# ai.net
KiCad netlist of a schematic drawn in Altium Designer
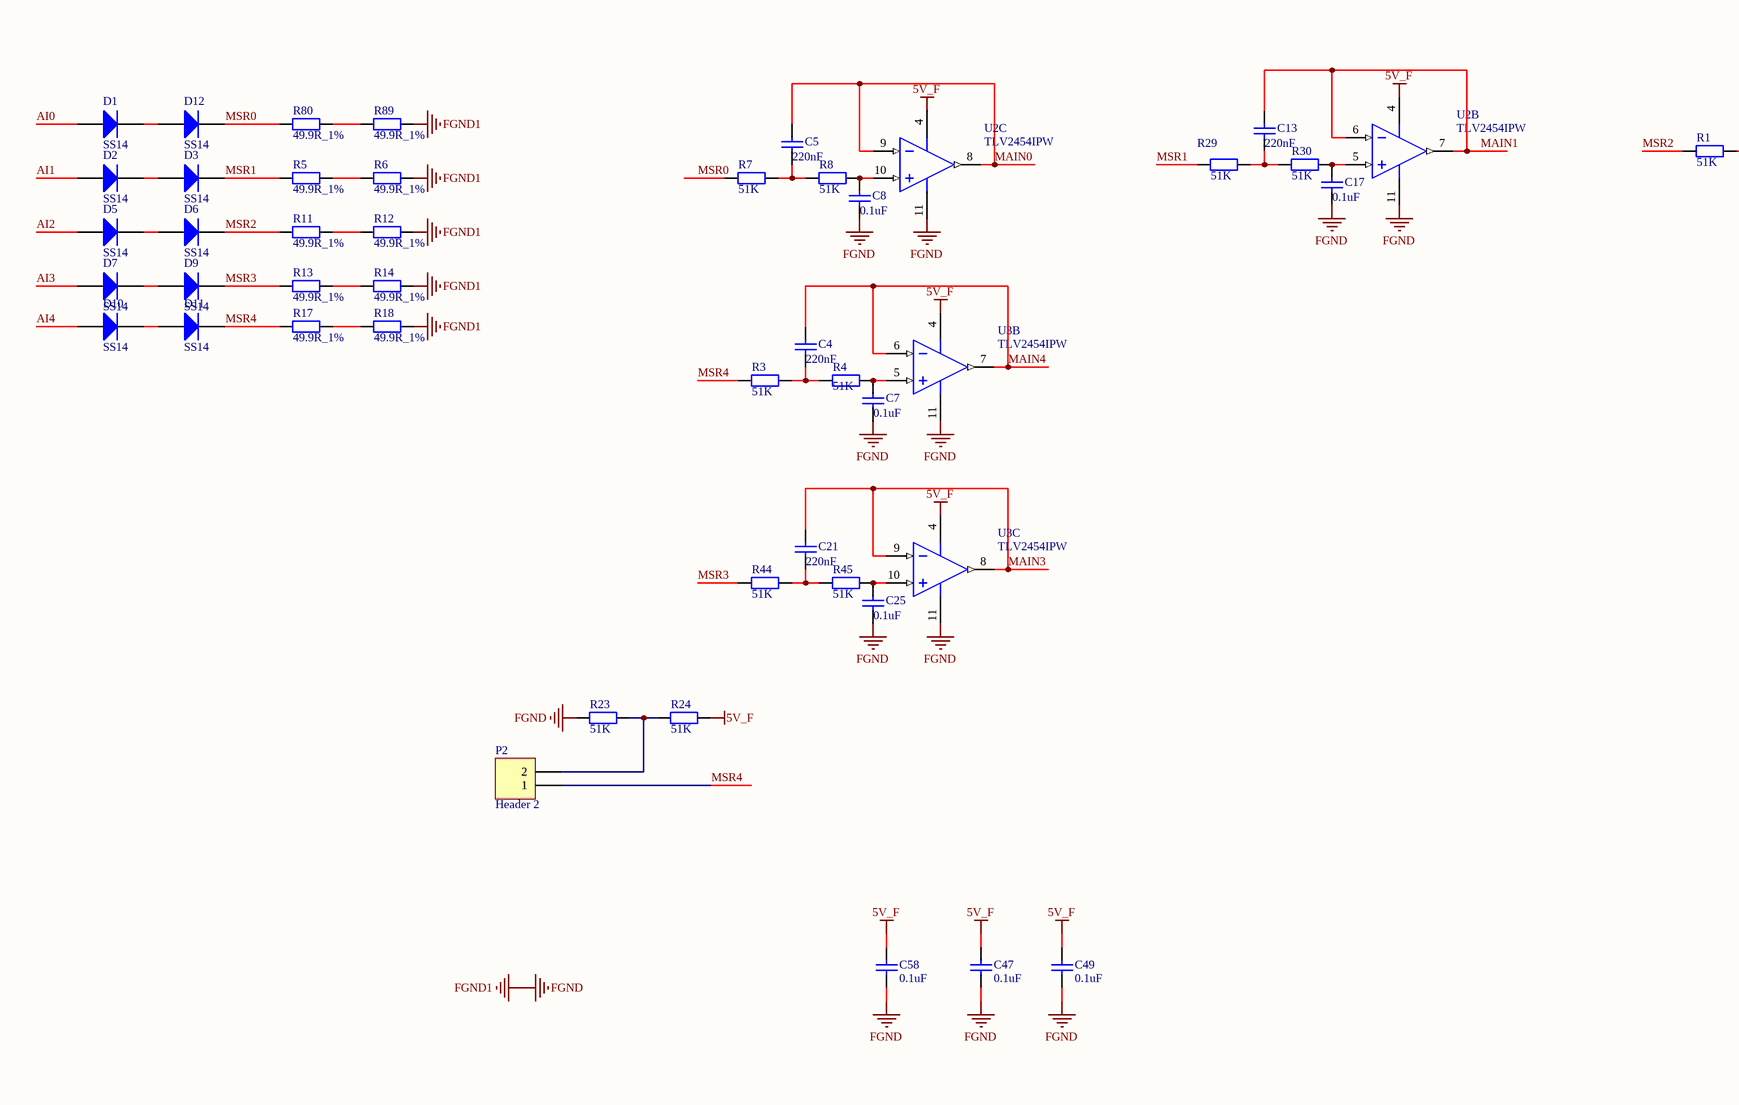
[diagram p0: ai.SchDoc, top left]
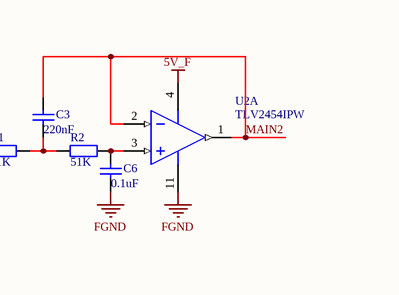
[diagram p1: ai.SchDoc, top right]
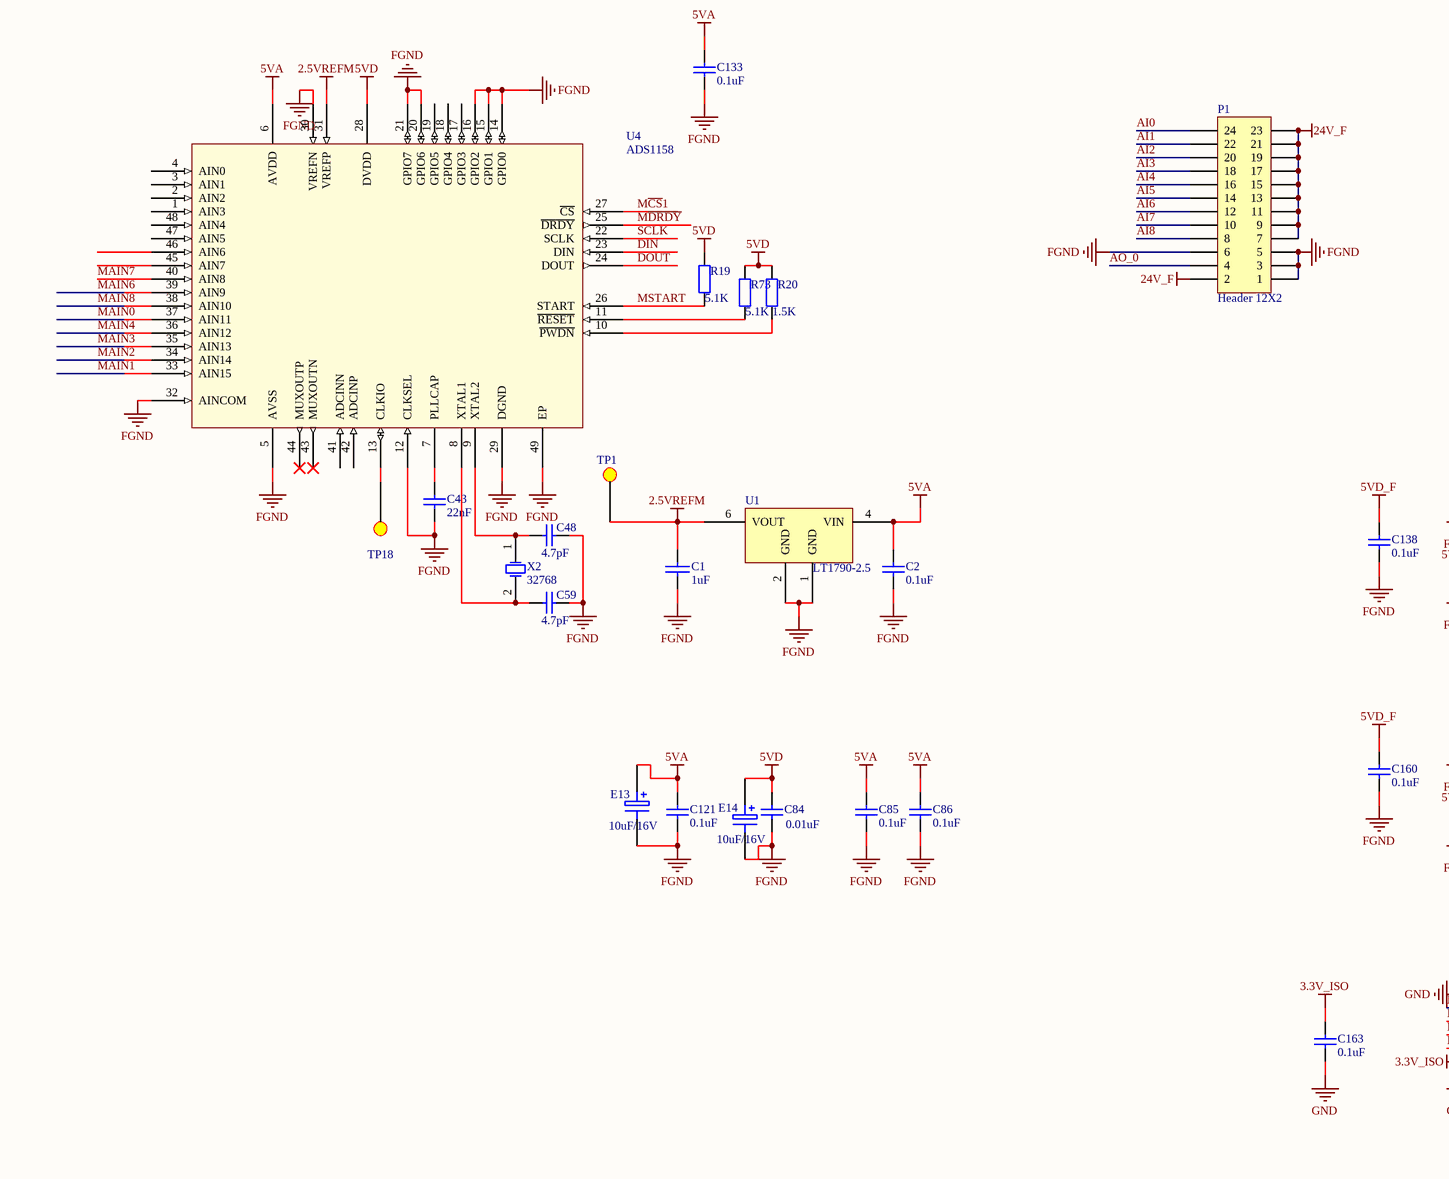
[diagram p2: ai.SchDoc, bottom left]
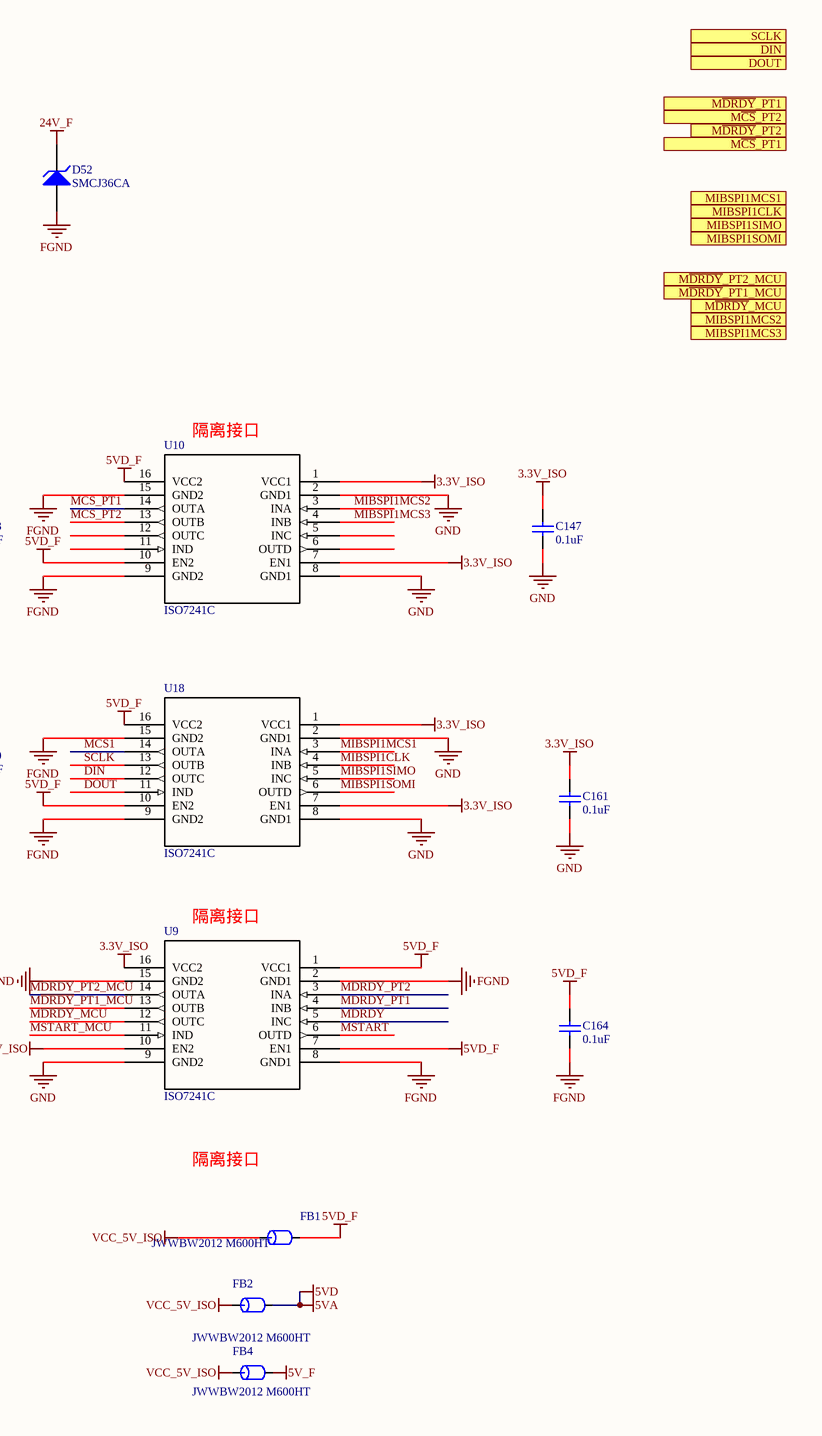
[diagram p3: ai.SchDoc, bottom right]

(export (version "E")
  (design (tool "Eeschema 10.0.6"))
  (components
    (comp (ref "C1")
      (value "1uF")
      (footprint "0603C")
      (description "Capacitor")
      (libsource (lib "*") (part "CAP"))
    )
    (comp (ref "C2")
      (value "0.1uF")
      (footprint "0603C")
      (description "Capacitor")
      (fields (field (name "PUBLISHER") "Altium Limited"))
      (libsource (lib "Miscellaneous Devices") (part "Cap"))
    )
    (comp (ref "C3")
      (value "220nF")
      (footprint "0805C")
      (description "Capacitor")
      (fields (field (name "PUBLISHER") "Altium Limited"))
      (libsource (lib "Miscellaneous Devices") (part "Cap"))
    )
    (comp (ref "C4")
      (value "220nF")
      (footprint "0805C")
      (description "Capacitor")
      (fields (field (name "PUBLISHER") "Altium Limited"))
      (libsource (lib "Miscellaneous Devices") (part "Cap"))
    )
    (comp (ref "C5")
      (value "220nF")
      (footprint "0805C")
      (description "Capacitor")
      (fields (field (name "PUBLISHER") "Altium Limited"))
      (libsource (lib "Miscellaneous Devices") (part "Cap"))
    )
    (comp (ref "C6")
      (value "0.1uF")
      (footprint "0603C")
      (description "Capacitor")
      (fields (field (name "PUBLISHER") "Altium Limited"))
      (libsource (lib "Miscellaneous Devices") (part "Cap"))
    )
    (comp (ref "C7")
      (value "0.1uF")
      (footprint "0603C")
      (description "Capacitor")
      (fields (field (name "PUBLISHER") "Altium Limited"))
      (libsource (lib "Miscellaneous Devices") (part "Cap"))
    )
    (comp (ref "C8")
      (value "0.1uF")
      (footprint "0603C")
      (description "Capacitor")
      (fields (field (name "PUBLISHER") "Altium Limited"))
      (libsource (lib "Miscellaneous Devices") (part "Cap"))
    )
    (comp (ref "C13")
      (value "220nF")
      (footprint "0805C")
      (description "Capacitor")
      (fields (field (name "PUBLISHER") "Altium Limited"))
      (libsource (lib "Miscellaneous Devices") (part "Cap"))
    )
    (comp (ref "C17")
      (value "0.1uF")
      (footprint "0603C")
      (description "Capacitor")
      (fields (field (name "PUBLISHER") "Altium Limited"))
      (libsource (lib "Miscellaneous Devices") (part "Cap"))
    )
    (comp (ref "C21")
      (value "220nF")
      (footprint "0805C")
      (description "Capacitor")
      (fields (field (name "PUBLISHER") "Altium Limited"))
      (libsource (lib "Miscellaneous Devices") (part "Cap"))
    )
    (comp (ref "C25")
      (value "0.1uF")
      (footprint "0603C")
      (description "Capacitor")
      (fields (field (name "PUBLISHER") "Altium Limited"))
      (libsource (lib "Miscellaneous Devices") (part "Cap"))
    )
    (comp (ref "C43")
      (value "22nF")
      (footprint "0805C")
      (description "Capacitor")
      (fields (field (name "PUBLISHER") "Altium Limited"))
      (libsource (lib "Miscellaneous Devices") (part "Cap"))
    )
    (comp (ref "C47")
      (value "0.1uF")
      (footprint "0603C")
      (description "Capacitor")
      (fields (field (name "PUBLISHER") "Altium Limited"))
      (libsource (lib "Miscellaneous Devices") (part "Cap"))
    )
    (comp (ref "C48")
      (value "4.7pF")
      (footprint "0603C")
      (description "Capacitor")
      (fields (field (name "PUBLISHER") "Altium Limited"))
      (libsource (lib "Miscellaneous Devices") (part "Cap"))
    )
    (comp (ref "C49")
      (value "0.1uF")
      (footprint "0603C")
      (description "Capacitor")
      (fields (field (name "PUBLISHER") "Altium Limited"))
      (libsource (lib "Miscellaneous Devices") (part "Cap"))
    )
    (comp (ref "C58")
      (value "0.1uF")
      (footprint "0603C")
      (description "Capacitor")
      (fields (field (name "PUBLISHER") "Altium Limited"))
      (libsource (lib "Miscellaneous Devices") (part "Cap"))
    )
    (comp (ref "C59")
      (value "4.7pF")
      (footprint "0603C")
      (description "Capacitor")
      (fields (field (name "PUBLISHER") "Altium Limited"))
      (libsource (lib "Miscellaneous Devices") (part "Cap"))
    )
    (comp (ref "C84")
      (value "0.01uF")
      (footprint "0603C")
      (description "Capacitor")
      (fields (field (name "PUBLISHER") "Altium Limited"))
      (libsource (lib "Miscellaneous Devices") (part "Cap"))
    )
    (comp (ref "C85")
      (value "0.1uF")
      (footprint "0603C")
      (description "Capacitor")
      (fields (field (name "PUBLISHER") "Altium Limited"))
      (libsource (lib "Miscellaneous Devices") (part "Cap"))
    )
    (comp (ref "C86")
      (value "0.1uF")
      (footprint "0603C")
      (description "Capacitor")
      (fields (field (name "PUBLISHER") "Altium Limited"))
      (libsource (lib "Miscellaneous Devices") (part "Cap"))
    )
    (comp (ref "C121")
      (value "0.1uF")
      (footprint "0603C")
      (description "Capacitor")
      (fields (field (name "PUBLISHER") "Altium Limited"))
      (libsource (lib "Miscellaneous Devices") (part "Cap"))
    )
    (comp (ref "C133")
      (value "0.1uF")
      (footprint "0603C")
      (description "Capacitor")
      (fields (field (name "PUBLISHER") "Altium Limited"))
      (libsource (lib "Miscellaneous Devices") (part "Cap"))
    )
    (comp (ref "C138")
      (value "0.1uF")
      (footprint "0603C")
      (description "Capacitor")
      (fields (field (name "PUBLISHER") "Altium Limited"))
      (libsource (lib "Miscellaneous Devices") (part "Cap"))
    )
    (comp (ref "C147")
      (value "0.1uF")
      (footprint "0603C")
      (description "Capacitor")
      (fields (field (name "PUBLISHER") "Altium Limited"))
      (libsource (lib "Miscellaneous Devices") (part "Cap"))
    )
    (comp (ref "C160")
      (value "0.1uF")
      (footprint "0603C")
      (description "Capacitor")
      (fields (field (name "PUBLISHER") "Altium Limited"))
      (libsource (lib "Miscellaneous Devices") (part "Cap"))
    )
    (comp (ref "C161")
      (value "0.1uF")
      (footprint "0603C")
      (description "Capacitor")
      (fields (field (name "PUBLISHER") "Altium Limited"))
      (libsource (lib "Miscellaneous Devices") (part "Cap"))
    )
    (comp (ref "C163")
      (value "0.1uF")
      (footprint "0603C")
      (description "Capacitor")
      (fields (field (name "PUBLISHER") "Altium Limited"))
      (libsource (lib "Miscellaneous Devices") (part "Cap"))
    )
    (comp (ref "C164")
      (value "0.1uF")
      (footprint "0603C")
      (description "Capacitor")
      (fields (field (name "PUBLISHER") "Altium Limited"))
      (libsource (lib "Miscellaneous Devices") (part "Cap"))
    )
    (comp (ref "D1")
      (value "SS14")
      (footprint "DO-214AC")
      (description "Default Diode")
      (fields (field (name "PUBLISHER") "Altium Limited"))
      (libsource (lib "Miscellaneous Devices") (part "Diode"))
    )
    (comp (ref "D2")
      (value "SS14")
      (footprint "DO-214AC")
      (description "Default Diode")
      (fields (field (name "PUBLISHER") "Altium Limited"))
      (libsource (lib "Miscellaneous Devices") (part "Diode"))
    )
    (comp (ref "D3")
      (value "SS14")
      (footprint "DO-214AC")
      (description "Default Diode")
      (fields (field (name "PUBLISHER") "Altium Limited"))
      (libsource (lib "Miscellaneous Devices") (part "Diode"))
    )
    (comp (ref "D5")
      (value "SS14")
      (footprint "DO-214AC")
      (description "Default Diode")
      (fields (field (name "PUBLISHER") "Altium Limited"))
      (libsource (lib "Miscellaneous Devices") (part "Diode"))
    )
    (comp (ref "D6")
      (value "SS14")
      (footprint "DO-214AC")
      (description "Default Diode")
      (fields (field (name "PUBLISHER") "Altium Limited"))
      (libsource (lib "Miscellaneous Devices") (part "Diode"))
    )
    (comp (ref "D7")
      (value "SS14")
      (footprint "DO-214AC")
      (description "Default Diode")
      (fields (field (name "PUBLISHER") "Altium Limited"))
      (libsource (lib "Miscellaneous Devices") (part "Diode"))
    )
    (comp (ref "D9")
      (value "SS14")
      (footprint "DO-214AC")
      (description "Default Diode")
      (fields (field (name "PUBLISHER") "Altium Limited"))
      (libsource (lib "Miscellaneous Devices") (part "Diode"))
    )
    (comp (ref "D10")
      (value "SS14")
      (footprint "DO-214AC")
      (description "Default Diode")
      (fields (field (name "PUBLISHER") "Altium Limited"))
      (libsource (lib "Miscellaneous Devices") (part "Diode"))
    )
    (comp (ref "D11")
      (value "SS14")
      (footprint "DO-214AC")
      (description "Default Diode")
      (fields (field (name "PUBLISHER") "Altium Limited"))
      (libsource (lib "Miscellaneous Devices") (part "Diode"))
    )
    (comp (ref "D12")
      (value "SS14")
      (footprint "DO-214AC")
      (description "Default Diode")
      (fields (field (name "PUBLISHER") "Altium Limited"))
      (libsource (lib "Miscellaneous Devices") (part "Diode"))
    )
    (comp (ref "D52")
      (value "SMCJ36CA")
      (footprint "SMC")
      (description "SMBJ36CA")
      (fields (field (name "PUBLISHER") "Altium Limited"))
      (libsource (lib "Miscellaneous Devices") (part "D Zener"))
    )
    (comp (ref "E13")
      (value "10uF/16V")
      (footprint "C3528")
      (description "Electrolytic Capacitor")
      (libsource (lib "*") (part "ELECTRO1"))
    )
    (comp (ref "E14")
      (value "10uF/16V")
      (footprint "C3528")
      (description "Electrolytic Capacitor")
      (libsource (lib "*") (part "ELECTRO1"))
    )
    (comp (ref "FB1")
      (value "JWWBW2012 M600HT")
      (footprint "0805R")
      (libsource (lib "Schlib_20110825") (part "FB"))
    )
    (comp (ref "FB2")
      (value "JWWBW2012 M600HT")
      (footprint "0805R")
      (libsource (lib "Schlib_20110825") (part "FB"))
    )
    (comp (ref "FB4")
      (value "JWWBW2012 M600HT")
      (footprint "0805R")
      (libsource (lib "Schlib_20110825") (part "FB"))
    )
    (comp (ref "P1")
      (value "Header 12X2")
      (footprint "XH2.54_2x12")
      (description "Header, 12-Pin, Dual row")
      (fields (field (name "PUBLISHER") "Altium Limited"))
      (libsource (lib "Miscellaneous Connectors") (part "Header 12X2"))
    )
    (comp (ref "P2")
      (value "Header 2")
      (footprint "HDR1X2")
      (description "Header, 2-Pin")
      (fields (field (name "PUBLISHER") "Altium Limited"))
      (libsource (lib "Miscellaneous Connectors") (part "Header 2"))
    )
    (comp (ref "R1") (value "51K") (footprint "0603R") (libsource (lib "MQlibrary") (part "Res0805M")))
    (comp (ref "R2") (value "51K") (footprint "0603R") (libsource (lib "MQlibrary") (part "Res0805M")))
    (comp (ref "R3") (value "51K") (footprint "0603R") (libsource (lib "MQlibrary") (part "Res0805M")))
    (comp (ref "R4") (value "51K") (footprint "0603R") (libsource (lib "MQlibrary") (part "Res0805M")))
    (comp (ref "R5") (value "49.9R_1%") (footprint "0805R") (libsource (lib "MQlibrary") (part "Res0805M")))
    (comp (ref "R6") (value "49.9R_1%") (footprint "0805R") (libsource (lib "MQlibrary") (part "Res0805M")))
    (comp (ref "R7") (value "51K") (footprint "0603R") (libsource (lib "MQlibrary") (part "Res0805M")))
    (comp (ref "R8") (value "51K") (footprint "0603R") (libsource (lib "MQlibrary") (part "Res0805M")))
    (comp (ref "R11") (value "49.9R_1%") (footprint "0805R") (libsource (lib "MQlibrary") (part "Res0805M")))
    (comp (ref "R12") (value "49.9R_1%") (footprint "0805R") (libsource (lib "MQlibrary") (part "Res0805M")))
    (comp (ref "R13") (value "49.9R_1%") (footprint "0805R") (libsource (lib "MQlibrary") (part "Res0805M")))
    (comp (ref "R14") (value "49.9R_1%") (footprint "0805R") (libsource (lib "MQlibrary") (part "Res0805M")))
    (comp (ref "R17") (value "49.9R_1%") (footprint "0805R") (libsource (lib "MQlibrary") (part "Res0805M")))
    (comp (ref "R18") (value "49.9R_1%") (footprint "0805R") (libsource (lib "MQlibrary") (part "Res0805M")))
    (comp (ref "R19") (value "5.1K") (footprint "0603R") (libsource (lib "") (part "Res0805M_1")))
    (comp (ref "R20") (value "1.5K") (footprint "0603R") (libsource (lib "") (part "Res0805M_1")))
    (comp (ref "R23") (value "51K") (footprint "0603R") (libsource (lib "") (part "Res0805M_2")))
    (comp (ref "R24") (value "51K") (footprint "0603R") (libsource (lib "") (part "Res0805M_2")))
    (comp (ref "R29") (value "51K") (footprint "0603R") (libsource (lib "MQlibrary") (part "Res0805M")))
    (comp (ref "R30") (value "51K") (footprint "0603R") (libsource (lib "MQlibrary") (part "Res0805M")))
    (comp (ref "R44") (value "51K") (footprint "0603R") (libsource (lib "MQlibrary") (part "Res0805M")))
    (comp (ref "R45") (value "51K") (footprint "0603R") (libsource (lib "MQlibrary") (part "Res0805M")))
    (comp (ref "R73") (value "5.1K") (footprint "0603R") (libsource (lib "") (part "Res0805M_1")))
    (comp (ref "R80") (value "49.9R_1%") (footprint "0805R") (libsource (lib "MQlibrary") (part "Res0805M")))
    (comp (ref "R89") (value "49.9R_1%") (footprint "0805R") (libsource (lib "MQlibrary") (part "Res0805M")))
    (comp (ref "TP1")
      (value "TEST_POINT")
      (footprint "TPD")
      (libsource (lib "基带芯片OEM板_V1P0_张猛_20120921") (part "TEST_POINT"))
    )
    (comp (ref "TP18")
      (value "TEST_POINT")
      (footprint "TPD")
      (libsource (lib "基带芯片OEM板_V1P0_张猛_20120921") (part "TEST_POINT"))
    )
    (comp (ref "U1")
      (value "LT1790-2.5")
      (footprint "SOT23-6")
      (description "2.5V Micropower SOT-23  Low Dropout Reference")
      (libsource (lib "Schlib") (part "LT1790-2.5"))
    )
    (comp (ref "U2")
      (value "TLV2454IPW")
      (footprint "TSSOP14")
      (description "Quad High-speed, Ultra Low-power, Single-Supply TTL comparator")
      (fields (field (name "PUBLISHER") "Altium Limited"))
      (libsource (lib "Maxim Analog Comparator") (part "MAX908EPD"))
    )
    (comp (ref "U3")
      (value "TLV2454IPW")
      (footprint "TSSOP14")
      (description "Quad High-speed, Ultra Low-power, Single-Supply TTL comparator")
      (fields (field (name "PUBLISHER") "Altium Limited"))
      (libsource (lib "Maxim Analog Comparator") (part "MAX908EPD"))
    )
    (comp (ref "U4")
      (value "ADS1158")
      (footprint "S-PVFQN-N48")
      (description "16-Channel, 16-Bit Analog-to-Digital Converter")
      (libsource (lib "Schlib") (part "ADS1158"))
    )
    (comp (ref "U9") (value "ISO7241C") (footprint "SOIC16") (libsource (lib "DI16") (part "ISO7241C")))
    (comp (ref "U10") (value "ISO7241C") (footprint "SOIC16") (libsource (lib "DI16") (part "ISO7241C")))
    (comp (ref "U18") (value "ISO7241C") (footprint "SOIC16") (libsource (lib "DI16") (part "ISO7241C")))
    (comp (ref "X2")
      (value "32768")
      (footprint "A")
      (description "Crystal Oscillator")
      (fields (field (name "PUBLISHER") "Altium Limited"))
      (libsource (lib "Miscellaneous Devices") (part "XTAL"))
    )
  )
  (nets
    (net (code "1") (name "/AI0") (class "Default")
      (node (ref "D1") (pin "1") (pinfunction "A_1") (pintype "passive"))
      (node (ref "P1") (pin "24") (pinfunction "24_24") (pintype "passive"))
    )
    (net (code "2") (name "/AI1") (class "Default")
      (node (ref "D2") (pin "1") (pinfunction "A_1") (pintype "passive"))
      (node (ref "P1") (pin "22") (pinfunction "22_22") (pintype "passive"))
    )
    (net (code "3") (name "/AI2") (class "Default")
      (node (ref "D5") (pin "1") (pinfunction "A_1") (pintype "passive"))
      (node (ref "P1") (pin "20") (pinfunction "20_20") (pintype "passive"))
    )
    (net (code "4") (name "/AI3") (class "Default")
      (node (ref "D7") (pin "1") (pinfunction "A_1") (pintype "passive"))
      (node (ref "P1") (pin "18") (pinfunction "18_18") (pintype "passive"))
    )
    (net (code "5") (name "/AI4") (class "Default")
      (node (ref "D10") (pin "1") (pinfunction "A_1") (pintype "passive"))
      (node (ref "P1") (pin "16") (pinfunction "16_16") (pintype "passive"))
    )
    (net (code "6") (name "/AI5") (class "Default")
      (node (ref "P1") (pin "14") (pinfunction "14_14") (pintype "passive"))
    )
    (net (code "7") (name "/AI6") (class "Default")
      (node (ref "P1") (pin "12") (pinfunction "12_12") (pintype "passive"))
    )
    (net (code "8") (name "/AI7") (class "Default")
      (node (ref "P1") (pin "10") (pinfunction "10_10") (pintype "passive"))
    )
    (net (code "9") (name "/AI8") (class "Default")
      (node (ref "P1") (pin "8") (pinfunction "8_8") (pintype "passive"))
    )
    (net (code "10") (name "/AO_0") (class "Default")
      (node (ref "P1") (pin "4") (pinfunction "4_4") (pintype "passive"))
    )
    (net (code "11") (name "/DIN") (class "Default")
      (node (ref "U18") (pin "12") (pinfunction "OUTC_12") (pintype "output"))
      (node (ref "U4") (pin "23") (pinfunction "DIN_23") (pintype "input"))
    )
    (net (code "12") (name "/DOUT") (class "Default")
      (node (ref "U18") (pin "11") (pinfunction "IND_11") (pintype "input"))
      (node (ref "U4") (pin "24") (pinfunction "DOUT_24") (pintype "output"))
    )
    (net (code "13") (name "/MAIN0") (class "Default")
      (node (ref "C5") (pin "2") (pinfunction "2_2") (pintype "passive"))
      (node (ref "U2") (pin "8") (pinfunction "OUT_8") (pintype "output"))
      (node (ref "U2") (pin "9") (pinfunction "IN-_9") (pintype "input"))
      (node (ref "U4") (pin "37") (pinfunction "AIN11_37") (pintype "input"))
    )
    (net (code "14") (name "/MAIN1") (class "Default")
      (node (ref "C13") (pin "2") (pinfunction "2_2") (pintype "passive"))
      (node (ref "U2") (pin "6") (pinfunction "IN-_6") (pintype "input"))
      (node (ref "U2") (pin "7") (pinfunction "OUT_7") (pintype "output"))
      (node (ref "U4") (pin "33") (pinfunction "AIN15_33") (pintype "input"))
    )
    (net (code "15") (name "/MAIN2") (class "Default")
      (node (ref "C3") (pin "2") (pinfunction "2_2") (pintype "passive"))
      (node (ref "U2") (pin "1") (pinfunction "OUT_1") (pintype "output"))
      (node (ref "U2") (pin "2") (pinfunction "IN-_2") (pintype "input"))
      (node (ref "U4") (pin "34") (pinfunction "AIN14_34") (pintype "input"))
    )
    (net (code "16") (name "/MAIN3") (class "Default")
      (node (ref "C21") (pin "2") (pinfunction "2_2") (pintype "passive"))
      (node (ref "U3") (pin "8") (pinfunction "OUT_8") (pintype "output"))
      (node (ref "U3") (pin "9") (pinfunction "IN-_9") (pintype "input"))
      (node (ref "U4") (pin "35") (pinfunction "AIN13_35") (pintype "input"))
    )
    (net (code "17") (name "/MAIN4") (class "Default")
      (node (ref "C4") (pin "2") (pinfunction "2_2") (pintype "passive"))
      (node (ref "U3") (pin "6") (pinfunction "IN-_6") (pintype "input"))
      (node (ref "U3") (pin "7") (pinfunction "OUT_7") (pintype "output"))
      (node (ref "U4") (pin "36") (pinfunction "AIN12_36") (pintype "input"))
    )
    (net (code "18") (name "/MAIN6") (class "Default")
      (node (ref "U4") (pin "39") (pinfunction "AIN9_39") (pintype "input"))
    )
    (net (code "19") (name "/MAIN7") (class "Default")
      (node (ref "U4") (pin "40") (pinfunction "AIN8_40") (pintype "input"))
    )
    (net (code "20") (name "/MAIN8") (class "Default")
      (node (ref "U4") (pin "38") (pinfunction "AIN10_38") (pintype "input"))
    )
    (net (code "21") (name "/MIBSPI1CLK") (class "Default")
      (node (ref "U18") (pin "4") (pinfunction "INB_4") (pintype "input"))
    )
    (net (code "22") (name "/MIBSPI1MCS1") (class "Default")
      (node (ref "U18") (pin "3") (pinfunction "INA_3") (pintype "input"))
    )
    (net (code "23") (name "/MIBSPI1MCS2") (class "Default")
      (node (ref "U10") (pin "3") (pinfunction "INA_3") (pintype "input"))
    )
    (net (code "24") (name "/MIBSPI1MCS3") (class "Default")
      (node (ref "U10") (pin "4") (pinfunction "INB_4") (pintype "input"))
    )
    (net (code "25") (name "/MIBSPI1SIMO") (class "Default")
      (node (ref "U18") (pin "5") (pinfunction "INC_5") (pintype "input"))
    )
    (net (code "26") (name "/MIBSPI1SOMI") (class "Default")
      (node (ref "U18") (pin "6") (pinfunction "OUTD_6") (pintype "output"))
    )
    (net (code "27") (name "/MSR0") (class "Default")
      (node (ref "D12") (pin "2") (pinfunction "K_2") (pintype "passive"))
      (node (ref "R7") (pin "2") (pinfunction "2_2") (pintype "passive"))
      (node (ref "R80") (pin "2") (pinfunction "2_2") (pintype "passive"))
    )
    (net (code "28") (name "/MSR1") (class "Default")
      (node (ref "D3") (pin "2") (pinfunction "K_2") (pintype "passive"))
      (node (ref "R29") (pin "2") (pinfunction "2_2") (pintype "passive"))
      (node (ref "R5") (pin "2") (pinfunction "2_2") (pintype "passive"))
    )
    (net (code "29") (name "/MSR2") (class "Default")
      (node (ref "D6") (pin "2") (pinfunction "K_2") (pintype "passive"))
      (node (ref "R1") (pin "2") (pinfunction "2_2") (pintype "passive"))
      (node (ref "R11") (pin "2") (pinfunction "2_2") (pintype "passive"))
    )
    (net (code "30") (name "/MSR3") (class "Default")
      (node (ref "D9") (pin "2") (pinfunction "K_2") (pintype "passive"))
      (node (ref "R13") (pin "2") (pinfunction "2_2") (pintype "passive"))
      (node (ref "R44") (pin "2") (pinfunction "2_2") (pintype "passive"))
    )
    (net (code "31") (name "/MSR4") (class "Default")
      (node (ref "D11") (pin "2") (pinfunction "K_2") (pintype "passive"))
      (node (ref "P2") (pin "1") (pinfunction "1_1") (pintype "passive"))
      (node (ref "R17") (pin "2") (pinfunction "2_2") (pintype "passive"))
      (node (ref "R3") (pin "2") (pinfunction "2_2") (pintype "passive"))
    )
    (net (code "32") (name "/MSTART") (class "Default")
      (node (ref "R19") (pin "2") (pinfunction "2_2") (pintype "passive"))
      (node (ref "U4") (pin "26") (pinfunction "START_26") (pintype "input"))
      (node (ref "U9") (pin "6") (pinfunction "OUTD_6") (pintype "output"))
    )
    (net (code "33") (name "/MSTART_MCU") (class "Default")
      (node (ref "U9") (pin "11") (pinfunction "IND_11") (pintype "input"))
    )
    (net (code "34") (name "/M~{CS}1") (class "Default")
      (node (ref "U18") (pin "14") (pinfunction "OUTA_14") (pintype "output"))
      (node (ref "U4") (pin "27") (pinfunction "~{CS}_27") (pintype "input"))
    )
    (net (code "35") (name "/M~{CS}_PT1") (class "Default")
      (node (ref "U10") (pin "14") (pinfunction "OUTA_14") (pintype "output"))
    )
    (net (code "36") (name "/M~{CS}_PT2") (class "Default")
      (node (ref "U10") (pin "13") (pinfunction "OUTB_13") (pintype "output"))
    )
    (net (code "37") (name "/M~{DRDY}") (class "Default")
      (node (ref "U4") (pin "25") (pinfunction "~{DRDY}_25") (pintype "output"))
      (node (ref "U9") (pin "5") (pinfunction "INC_5") (pintype "input"))
    )
    (net (code "38") (name "/M~{DRDY}_MCU") (class "Default")
      (node (ref "U9") (pin "12") (pinfunction "OUTC_12") (pintype "output"))
    )
    (net (code "39") (name "/M~{DRDY}_PT1") (class "Default")
      (node (ref "U9") (pin "4") (pinfunction "INB_4") (pintype "input"))
    )
    (net (code "40") (name "/M~{DRDY}_PT1_MCU") (class "Default")
      (node (ref "U9") (pin "13") (pinfunction "OUTB_13") (pintype "output"))
    )
    (net (code "41") (name "/M~{DRDY}_PT2") (class "Default")
      (node (ref "U9") (pin "3") (pinfunction "INA_3") (pintype "input"))
    )
    (net (code "42") (name "/M~{DRDY}_PT2_MCU") (class "Default")
      (node (ref "U9") (pin "14") (pinfunction "OUTA_14") (pintype "output"))
    )
    (net (code "43") (name "/SCLK") (class "Default")
      (node (ref "U18") (pin "13") (pinfunction "OUTB_13") (pintype "output"))
      (node (ref "U4") (pin "22") (pinfunction "SCLK_22") (pintype "input"))
    )
    (net (code "44") (name "2.5VREFM") (class "Default")
      (node (ref "C1") (pin "1") (pinfunction "1_1") (pintype "passive"))
      (node (ref "TP1") (pin "1") (pinfunction "1_1") (pintype "passive"))
      (node (ref "U1") (pin "6") (pinfunction "VOUT_6") (pintype "power_in"))
      (node (ref "U4") (pin "31") (pinfunction "VREFP_31") (pintype "input"))
    )
    (net (code "45") (name "3.3V_ISO") (class "Default")
      (node (ref "C147") (pin "2") (pinfunction "2_2") (pintype "passive"))
      (node (ref "C161") (pin "2") (pinfunction "2_2") (pintype "passive"))
      (node (ref "C163") (pin "2") (pinfunction "2_2") (pintype "passive"))
      (node (ref "U10") (pin "1") (pinfunction "VCC1_1") (pintype "power_in"))
      (node (ref "U10") (pin "7") (pinfunction "EN1_7") (pintype "passive"))
      (node (ref "U18") (pin "1") (pinfunction "VCC1_1") (pintype "power_in"))
      (node (ref "U18") (pin "7") (pinfunction "EN1_7") (pintype "passive"))
      (node (ref "U9") (pin "10") (pinfunction "EN2_10") (pintype "passive"))
      (node (ref "U9") (pin "16") (pinfunction "VCC2_16") (pintype "power_in"))
    )
    (net (code "46") (name "5VA") (class "Default")
      (node (ref "C121") (pin "2") (pinfunction "2_2") (pintype "passive"))
      (node (ref "C133") (pin "2") (pinfunction "2_2") (pintype "passive"))
      (node (ref "C2") (pin "2") (pinfunction "2_2") (pintype "passive"))
      (node (ref "C84") (pin "2") (pinfunction "2_2") (pintype "passive"))
      (node (ref "C85") (pin "2") (pinfunction "2_2") (pintype "passive"))
      (node (ref "C86") (pin "2") (pinfunction "2_2") (pintype "passive"))
      (node (ref "E13") (pin "1") (pinfunction "1_1") (pintype "passive"))
      (node (ref "E14") (pin "1") (pinfunction "1_1") (pintype "passive"))
      (node (ref "FB2") (pin "2") (pintype "passive"))
      (node (ref "R19") (pin "1") (pinfunction "1_1") (pintype "passive"))
      (node (ref "R20") (pin "1") (pinfunction "1_1") (pintype "passive"))
      (node (ref "R73") (pin "1") (pinfunction "1_1") (pintype "passive"))
      (node (ref "U1") (pin "4") (pinfunction "VIN_4") (pintype "power_in"))
      (node (ref "U4") (pin "28") (pinfunction "DVDD_28") (pintype "power_in"))
      (node (ref "U4") (pin "6") (pinfunction "AVDD_6") (pintype "passive"))
    )
    (net (code "47") (name "5VD_F") (class "Default")
      (node (ref "C138") (pin "2") (pinfunction "2_2") (pintype "passive"))
      (node (ref "C160") (pin "2") (pinfunction "2_2") (pintype "passive"))
      (node (ref "C164") (pin "2") (pinfunction "2_2") (pintype "passive"))
      (node (ref "FB1") (pin "2") (pintype "passive"))
      (node (ref "U10") (pin "10") (pinfunction "EN2_10") (pintype "passive"))
      (node (ref "U10") (pin "16") (pinfunction "VCC2_16") (pintype "power_in"))
      (node (ref "U18") (pin "10") (pinfunction "EN2_10") (pintype "passive"))
      (node (ref "U18") (pin "16") (pinfunction "VCC2_16") (pintype "power_in"))
      (node (ref "U9") (pin "1") (pinfunction "VCC1_1") (pintype "power_in"))
      (node (ref "U9") (pin "7") (pinfunction "EN1_7") (pintype "passive"))
    )
    (net (code "48") (name "5V_F") (class "Default")
      (node (ref "C47") (pin "2") (pinfunction "2_2") (pintype "passive"))
      (node (ref "C49") (pin "2") (pinfunction "2_2") (pintype "passive"))
      (node (ref "C58") (pin "2") (pinfunction "2_2") (pintype "passive"))
      (node (ref "FB4") (pin "2") (pintype "passive"))
      (node (ref "R24") (pin "2") (pinfunction "2_2") (pintype "passive"))
      (node (ref "U2") (pin "4") (pinfunction "V+_4") (pintype "power_in"))
      (node (ref "U3") (pin "4") (pinfunction "V+_4") (pintype "power_in"))
    )
    (net (code "49") (name "24V_F") (class "Default")
      (node (ref "D52") (pin "2") (pinfunction "K_2") (pintype "passive"))
      (node (ref "P1") (pin "11") (pinfunction "11_11") (pintype "passive"))
      (node (ref "P1") (pin "13") (pinfunction "13_13") (pintype "passive"))
      (node (ref "P1") (pin "15") (pinfunction "15_15") (pintype "passive"))
      (node (ref "P1") (pin "17") (pinfunction "17_17") (pintype "passive"))
      (node (ref "P1") (pin "19") (pinfunction "19_19") (pintype "passive"))
      (node (ref "P1") (pin "2") (pinfunction "2_2") (pintype "passive"))
      (node (ref "P1") (pin "21") (pinfunction "21_21") (pintype "passive"))
      (node (ref "P1") (pin "23") (pinfunction "23_23") (pintype "passive"))
      (node (ref "P1") (pin "7") (pinfunction "7_7") (pintype "passive"))
      (node (ref "P1") (pin "9") (pinfunction "9_9") (pintype "passive"))
    )
    (net (code "50") (name "FGND") (class "Default")
      (node (ref "C1") (pin "2") (pinfunction "2_2") (pintype "passive"))
      (node (ref "C121") (pin "1") (pinfunction "1_1") (pintype "passive"))
      (node (ref "C133") (pin "1") (pinfunction "1_1") (pintype "passive"))
      (node (ref "C138") (pin "1") (pinfunction "1_1") (pintype "passive"))
      (node (ref "C160") (pin "1") (pinfunction "1_1") (pintype "passive"))
      (node (ref "C164") (pin "1") (pinfunction "1_1") (pintype "passive"))
      (node (ref "C17") (pin "1") (pinfunction "1_1") (pintype "passive"))
      (node (ref "C2") (pin "1") (pinfunction "1_1") (pintype "passive"))
      (node (ref "C25") (pin "1") (pinfunction "1_1") (pintype "passive"))
      (node (ref "C43") (pin "2") (pinfunction "2_2") (pintype "passive"))
      (node (ref "C47") (pin "1") (pinfunction "1_1") (pintype "passive"))
      (node (ref "C48") (pin "2") (pinfunction "2_2") (pintype "passive"))
      (node (ref "C49") (pin "1") (pinfunction "1_1") (pintype "passive"))
      (node (ref "C58") (pin "1") (pinfunction "1_1") (pintype "passive"))
      (node (ref "C59") (pin "2") (pinfunction "2_2") (pintype "passive"))
      (node (ref "C6") (pin "1") (pinfunction "1_1") (pintype "passive"))
      (node (ref "C7") (pin "1") (pinfunction "1_1") (pintype "passive"))
      (node (ref "C8") (pin "1") (pinfunction "1_1") (pintype "passive"))
      (node (ref "C84") (pin "1") (pinfunction "1_1") (pintype "passive"))
      (node (ref "C85") (pin "1") (pinfunction "1_1") (pintype "passive"))
      (node (ref "C86") (pin "1") (pinfunction "1_1") (pintype "passive"))
      (node (ref "D52") (pin "1") (pinfunction "A_1") (pintype "passive"))
      (node (ref "E13") (pin "2") (pinfunction "2_2") (pintype "passive"))
      (node (ref "E14") (pin "2") (pinfunction "2_2") (pintype "passive"))
      (node (ref "P1") (pin "1") (pinfunction "1_1") (pintype "passive"))
      (node (ref "P1") (pin "3") (pinfunction "3_3") (pintype "passive"))
      (node (ref "P1") (pin "5") (pinfunction "5_5") (pintype "passive"))
      (node (ref "P1") (pin "6") (pinfunction "6_6") (pintype "passive"))
      (node (ref "R12") (pin "1") (pinfunction "1_1") (pintype "passive"))
      (node (ref "R14") (pin "1") (pinfunction "1_1") (pintype "passive"))
      (node (ref "R18") (pin "1") (pinfunction "1_1") (pintype "passive"))
      (node (ref "R23") (pin "1") (pinfunction "1_1") (pintype "passive"))
      (node (ref "R6") (pin "1") (pinfunction "1_1") (pintype "passive"))
      (node (ref "R89") (pin "1") (pinfunction "1_1") (pintype "passive"))
      (node (ref "U1") (pin "1") (pinfunction "GND_1") (pintype "power_in"))
      (node (ref "U1") (pin "2") (pinfunction "GND_2") (pintype "power_in"))
      (node (ref "U10") (pin "15") (pinfunction "GND2_15") (pintype "power_in"))
      (node (ref "U10") (pin "9") (pinfunction "GND2_9") (pintype "power_in"))
      (node (ref "U18") (pin "15") (pinfunction "GND2_15") (pintype "power_in"))
      (node (ref "U18") (pin "9") (pinfunction "GND2_9") (pintype "power_in"))
      (node (ref "U2") (pin "11") (pinfunction "GND_11") (pintype "power_in"))
      (node (ref "U3") (pin "11") (pinfunction "GND_11") (pintype "power_in"))
      (node (ref "U4") (pin "12") (pinfunction "CLKSEL_12") (pintype "input"))
      (node (ref "U4") (pin "14") (pinfunction "GPIO0_14") (pintype "bidirectional"))
      (node (ref "U4") (pin "15") (pinfunction "GPIO1_15") (pintype "bidirectional"))
      (node (ref "U4") (pin "16") (pinfunction "GPIO2_16") (pintype "bidirectional"))
      (node (ref "U4") (pin "20") (pinfunction "GPIO6_20") (pintype "bidirectional"))
      (node (ref "U4") (pin "21") (pinfunction "GPIO7_21") (pintype "bidirectional"))
      (node (ref "U4") (pin "29") (pinfunction "DGND_29") (pintype "power_in"))
      (node (ref "U4") (pin "30") (pinfunction "VREFN_30") (pintype "input"))
      (node (ref "U4") (pin "32") (pinfunction "AINCOM_32") (pintype "input"))
      (node (ref "U4") (pin "49") (pinfunction "EP_49") (pintype "passive"))
      (node (ref "U4") (pin "5") (pinfunction "AVSS_5") (pintype "power_in"))
      (node (ref "U9") (pin "2") (pinfunction "GND1_2") (pintype "power_in"))
      (node (ref "U9") (pin "8") (pinfunction "GND1_8") (pintype "power_in"))
    )
    (net (code "51") (name "GND") (class "Default")
      (node (ref "C147") (pin "1") (pinfunction "1_1") (pintype "passive"))
      (node (ref "C161") (pin "1") (pinfunction "1_1") (pintype "passive"))
      (node (ref "C163") (pin "1") (pinfunction "1_1") (pintype "passive"))
      (node (ref "U10") (pin "2") (pinfunction "GND1_2") (pintype "power_in"))
      (node (ref "U10") (pin "8") (pinfunction "GND1_8") (pintype "power_in"))
      (node (ref "U18") (pin "2") (pinfunction "GND1_2") (pintype "power_in"))
      (node (ref "U18") (pin "8") (pinfunction "GND1_8") (pintype "power_in"))
      (node (ref "U9") (pin "15") (pinfunction "GND2_15") (pintype "power_in"))
      (node (ref "U9") (pin "9") (pinfunction "GND2_9") (pintype "power_in"))
    )
    (net (code "52") (name "Net-(C3-Pad1)") (class "Default")
      (node (ref "C3") (pin "1") (pinfunction "1_1") (pintype "passive"))
      (node (ref "R1") (pin "1") (pinfunction "1_1") (pintype "passive"))
      (node (ref "R2") (pin "2") (pinfunction "2_2") (pintype "passive"))
    )
    (net (code "53") (name "Net-(C4-Pad1)") (class "Default")
      (node (ref "C4") (pin "1") (pinfunction "1_1") (pintype "passive"))
      (node (ref "R3") (pin "1") (pinfunction "1_1") (pintype "passive"))
      (node (ref "R4") (pin "2") (pinfunction "2_2") (pintype "passive"))
    )
    (net (code "54") (name "Net-(C5-Pad1)") (class "Default")
      (node (ref "C5") (pin "1") (pinfunction "1_1") (pintype "passive"))
      (node (ref "R7") (pin "1") (pinfunction "1_1") (pintype "passive"))
      (node (ref "R8") (pin "2") (pinfunction "2_2") (pintype "passive"))
    )
    (net (code "55") (name "Net-(C13-Pad1)") (class "Default")
      (node (ref "C13") (pin "1") (pinfunction "1_1") (pintype "passive"))
      (node (ref "R29") (pin "1") (pinfunction "1_1") (pintype "passive"))
      (node (ref "R30") (pin "2") (pinfunction "2_2") (pintype "passive"))
    )
    (net (code "56") (name "Net-(C21-Pad1)") (class "Default")
      (node (ref "C21") (pin "1") (pinfunction "1_1") (pintype "passive"))
      (node (ref "R44") (pin "1") (pinfunction "1_1") (pintype "passive"))
      (node (ref "R45") (pin "2") (pinfunction "2_2") (pintype "passive"))
    )
    (net (code "57") (name "Net-(D1-K)") (class "Default")
      (node (ref "D1") (pin "2") (pinfunction "K_2") (pintype "passive"))
      (node (ref "D12") (pin "1") (pinfunction "A_1") (pintype "passive"))
    )
    (net (code "58") (name "Net-(D2-K)") (class "Default")
      (node (ref "D2") (pin "2") (pinfunction "K_2") (pintype "passive"))
      (node (ref "D3") (pin "1") (pinfunction "A_1") (pintype "passive"))
    )
    (net (code "59") (name "Net-(D5-K)") (class "Default")
      (node (ref "D5") (pin "2") (pinfunction "K_2") (pintype "passive"))
      (node (ref "D6") (pin "1") (pinfunction "A_1") (pintype "passive"))
    )
    (net (code "60") (name "Net-(D7-K)") (class "Default")
      (node (ref "D7") (pin "2") (pinfunction "K_2") (pintype "passive"))
      (node (ref "D9") (pin "1") (pinfunction "A_1") (pintype "passive"))
    )
    (net (code "61") (name "Net-(D10-K)") (class "Default")
      (node (ref "D10") (pin "2") (pinfunction "K_2") (pintype "passive"))
      (node (ref "D11") (pin "1") (pinfunction "A_1") (pintype "passive"))
    )
    (net (code "62") (name "Net-(P2-Pad2)") (class "Default")
      (node (ref "P2") (pin "2") (pinfunction "2_2") (pintype "passive"))
      (node (ref "R23") (pin "2") (pinfunction "2_2") (pintype "passive"))
      (node (ref "R24") (pin "1") (pinfunction "1_1") (pintype "passive"))
    )
    (net (code "63") (name "Net-(R5-Pad1)") (class "Default")
      (node (ref "R5") (pin "1") (pinfunction "1_1") (pintype "passive"))
      (node (ref "R6") (pin "2") (pinfunction "2_2") (pintype "passive"))
    )
    (net (code "64") (name "Net-(R11-Pad1)") (class "Default")
      (node (ref "R11") (pin "1") (pinfunction "1_1") (pintype "passive"))
      (node (ref "R12") (pin "2") (pinfunction "2_2") (pintype "passive"))
    )
    (net (code "65") (name "Net-(R13-Pad1)") (class "Default")
      (node (ref "R13") (pin "1") (pinfunction "1_1") (pintype "passive"))
      (node (ref "R14") (pin "2") (pinfunction "2_2") (pintype "passive"))
    )
    (net (code "66") (name "Net-(R17-Pad1)") (class "Default")
      (node (ref "R17") (pin "1") (pinfunction "1_1") (pintype "passive"))
      (node (ref "R18") (pin "2") (pinfunction "2_2") (pintype "passive"))
    )
    (net (code "67") (name "Net-(R80-Pad1)") (class "Default")
      (node (ref "R80") (pin "1") (pinfunction "1_1") (pintype "passive"))
      (node (ref "R89") (pin "2") (pinfunction "2_2") (pintype "passive"))
    )
    (net (code "68") (name "Net-(U2A-IN+)") (class "Default")
      (node (ref "C6") (pin "2") (pinfunction "2_2") (pintype "passive"))
      (node (ref "R2") (pin "1") (pinfunction "1_1") (pintype "passive"))
      (node (ref "U2") (pin "3") (pinfunction "IN+_3") (pintype "input"))
    )
    (net (code "69") (name "Net-(U2B-IN+)") (class "Default")
      (node (ref "C17") (pin "2") (pinfunction "2_2") (pintype "passive"))
      (node (ref "R30") (pin "1") (pinfunction "1_1") (pintype "passive"))
      (node (ref "U2") (pin "5") (pinfunction "IN+_5") (pintype "input"))
    )
    (net (code "70") (name "Net-(U2C-IN+)") (class "Default")
      (node (ref "C8") (pin "2") (pinfunction "2_2") (pintype "passive"))
      (node (ref "R8") (pin "1") (pinfunction "1_1") (pintype "passive"))
      (node (ref "U2") (pin "10") (pinfunction "IN+_10") (pintype "input"))
    )
    (net (code "71") (name "Net-(U3B-IN+)") (class "Default")
      (node (ref "C7") (pin "2") (pinfunction "2_2") (pintype "passive"))
      (node (ref "R4") (pin "1") (pinfunction "1_1") (pintype "passive"))
      (node (ref "U3") (pin "5") (pinfunction "IN+_5") (pintype "input"))
    )
    (net (code "72") (name "Net-(U3C-IN+)") (class "Default")
      (node (ref "C25") (pin "2") (pinfunction "2_2") (pintype "passive"))
      (node (ref "R45") (pin "1") (pinfunction "1_1") (pintype "passive"))
      (node (ref "U3") (pin "10") (pinfunction "IN+_10") (pintype "input"))
    )
    (net (code "73") (name "Net-(U4-CLKIO)") (class "Default")
      (node (ref "TP18") (pin "1") (pinfunction "1_1") (pintype "passive"))
      (node (ref "U4") (pin "13") (pinfunction "CLKIO_13") (pintype "bidirectional"))
    )
    (net (code "74") (name "Net-(U4-PLLCAP)") (class "Default")
      (node (ref "C43") (pin "1") (pinfunction "1_1") (pintype "passive"))
      (node (ref "U4") (pin "7") (pinfunction "PLLCAP_7") (pintype "power_in"))
    )
    (net (code "75") (name "Net-(U4-XTAL1)") (class "Default")
      (node (ref "C59") (pin "1") (pinfunction "1_1") (pintype "passive"))
      (node (ref "U4") (pin "8") (pinfunction "XTAL1_8") (pintype "passive"))
      (node (ref "X2") (pin "2") (pinfunction "OSC2_2") (pintype "passive"))
    )
    (net (code "76") (name "Net-(U4-XTAL2)") (class "Default")
      (node (ref "C48") (pin "1") (pinfunction "1_1") (pintype "passive"))
      (node (ref "U4") (pin "9") (pinfunction "XTAL2_9") (pintype "passive"))
      (node (ref "X2") (pin "1") (pinfunction "OSC1_1") (pintype "passive"))
    )
    (net (code "77") (name "Net-(U4-~{PWDN})") (class "Default")
      (node (ref "R20") (pin "2") (pinfunction "2_2") (pintype "passive"))
      (node (ref "U4") (pin "10") (pinfunction "~{PWDN}_10") (pintype "input"))
    )
    (net (code "78") (name "Net-(U4-~{RESET})") (class "Default")
      (node (ref "R73") (pin "2") (pinfunction "2_2") (pintype "passive"))
      (node (ref "U4") (pin "11") (pinfunction "~{RESET}_11") (pintype "input"))
    )
    (net (code "79") (name "VCC_5V_ISO") (class "Default")
      (node (ref "FB1") (pin "1") (pintype "passive"))
      (node (ref "FB2") (pin "1") (pintype "passive"))
      (node (ref "FB4") (pin "1") (pintype "passive"))
    )
    (net (code "80") (name "unconnected-(U1-DNC-Pad3)") (class "Default")
      (node (ref "U1") (pin "3") (pinfunction "DNC_3") (pintype "passive"))
    )
    (net (code "81") (name "unconnected-(U1-DNC-Pad5)") (class "Default")
      (node (ref "U1") (pin "5") (pinfunction "DNC_5") (pintype "passive"))
    )
    (net (code "82") (name "unconnected-(U4-ADCINN-Pad41)") (class "Default")
      (node (ref "U4") (pin "41") (pinfunction "ADCINN_41") (pintype "input"))
    )
    (net (code "83") (name "unconnected-(U4-ADCINP-Pad42)") (class "Default")
      (node (ref "U4") (pin "42") (pinfunction "ADCINP_42") (pintype "input"))
    )
    (net (code "84") (name "unconnected-(U4-AIN0-Pad4)") (class "Default")
      (node (ref "U4") (pin "4") (pinfunction "AIN0_4") (pintype "input"))
    )
    (net (code "85") (name "unconnected-(U4-AIN1-Pad3)") (class "Default")
      (node (ref "U4") (pin "3") (pinfunction "AIN1_3") (pintype "input"))
    )
    (net (code "86") (name "unconnected-(U4-AIN2-Pad2)") (class "Default")
      (node (ref "U4") (pin "2") (pinfunction "AIN2_2") (pintype "input"))
    )
    (net (code "87") (name "unconnected-(U4-AIN3-Pad1)") (class "Default")
      (node (ref "U4") (pin "1") (pinfunction "AIN3_1") (pintype "input"))
    )
    (net (code "88") (name "unconnected-(U4-AIN4-Pad48)") (class "Default")
      (node (ref "U4") (pin "48") (pinfunction "AIN4_48") (pintype "input"))
    )
    (net (code "89") (name "unconnected-(U4-AIN5-Pad47)") (class "Default")
      (node (ref "U4") (pin "47") (pinfunction "AIN5_47") (pintype "input"))
    )
    (net (code "90") (name "unconnected-(U4-AIN6-Pad46)") (class "Default")
      (node (ref "U4") (pin "46") (pinfunction "AIN6_46") (pintype "input"))
    )
    (net (code "91") (name "unconnected-(U4-AIN7-Pad45)") (class "Default")
      (node (ref "U4") (pin "45") (pinfunction "AIN7_45") (pintype "input"))
    )
    (net (code "92") (name "unconnected-(U4-GPIO3-Pad17)") (class "Default")
      (node (ref "U4") (pin "17") (pinfunction "GPIO3_17") (pintype "bidirectional"))
    )
    (net (code "93") (name "unconnected-(U4-GPIO4-Pad18)") (class "Default")
      (node (ref "U4") (pin "18") (pinfunction "GPIO4_18") (pintype "bidirectional"))
    )
    (net (code "94") (name "unconnected-(U4-GPIO5-Pad19)") (class "Default")
      (node (ref "U4") (pin "19") (pinfunction "GPIO5_19") (pintype "bidirectional"))
    )
    (net (code "95") (name "unconnected-(U4-MUXOUTN-Pad43)") (class "Default")
      (node (ref "U4") (pin "43") (pinfunction "MUXOUTN_43") (pintype "output+no_connect"))
    )
    (net (code "96") (name "unconnected-(U4-MUXOUTP-Pad44)") (class "Default")
      (node (ref "U4") (pin "44") (pinfunction "MUXOUTP_44") (pintype "output+no_connect"))
    )
    (net (code "97") (name "unconnected-(U10-INC-Pad5)") (class "Default")
      (node (ref "U10") (pin "5") (pinfunction "INC_5") (pintype "input"))
    )
    (net (code "98") (name "unconnected-(U10-IND-Pad11)") (class "Default")
      (node (ref "U10") (pin "11") (pinfunction "IND_11") (pintype "input"))
    )
    (net (code "99") (name "unconnected-(U10-OUTC-Pad12)") (class "Default")
      (node (ref "U10") (pin "12") (pinfunction "OUTC_12") (pintype "output"))
    )
    (net (code "100") (name "unconnected-(U10-OUTD-Pad6)") (class "Default")
      (node (ref "U10") (pin "6") (pinfunction "OUTD_6") (pintype "output"))
    )
  )
)
